# WidgetArduinoProMiniBreakout.net
KiCad netlist of a schematic drawn in EAGLE
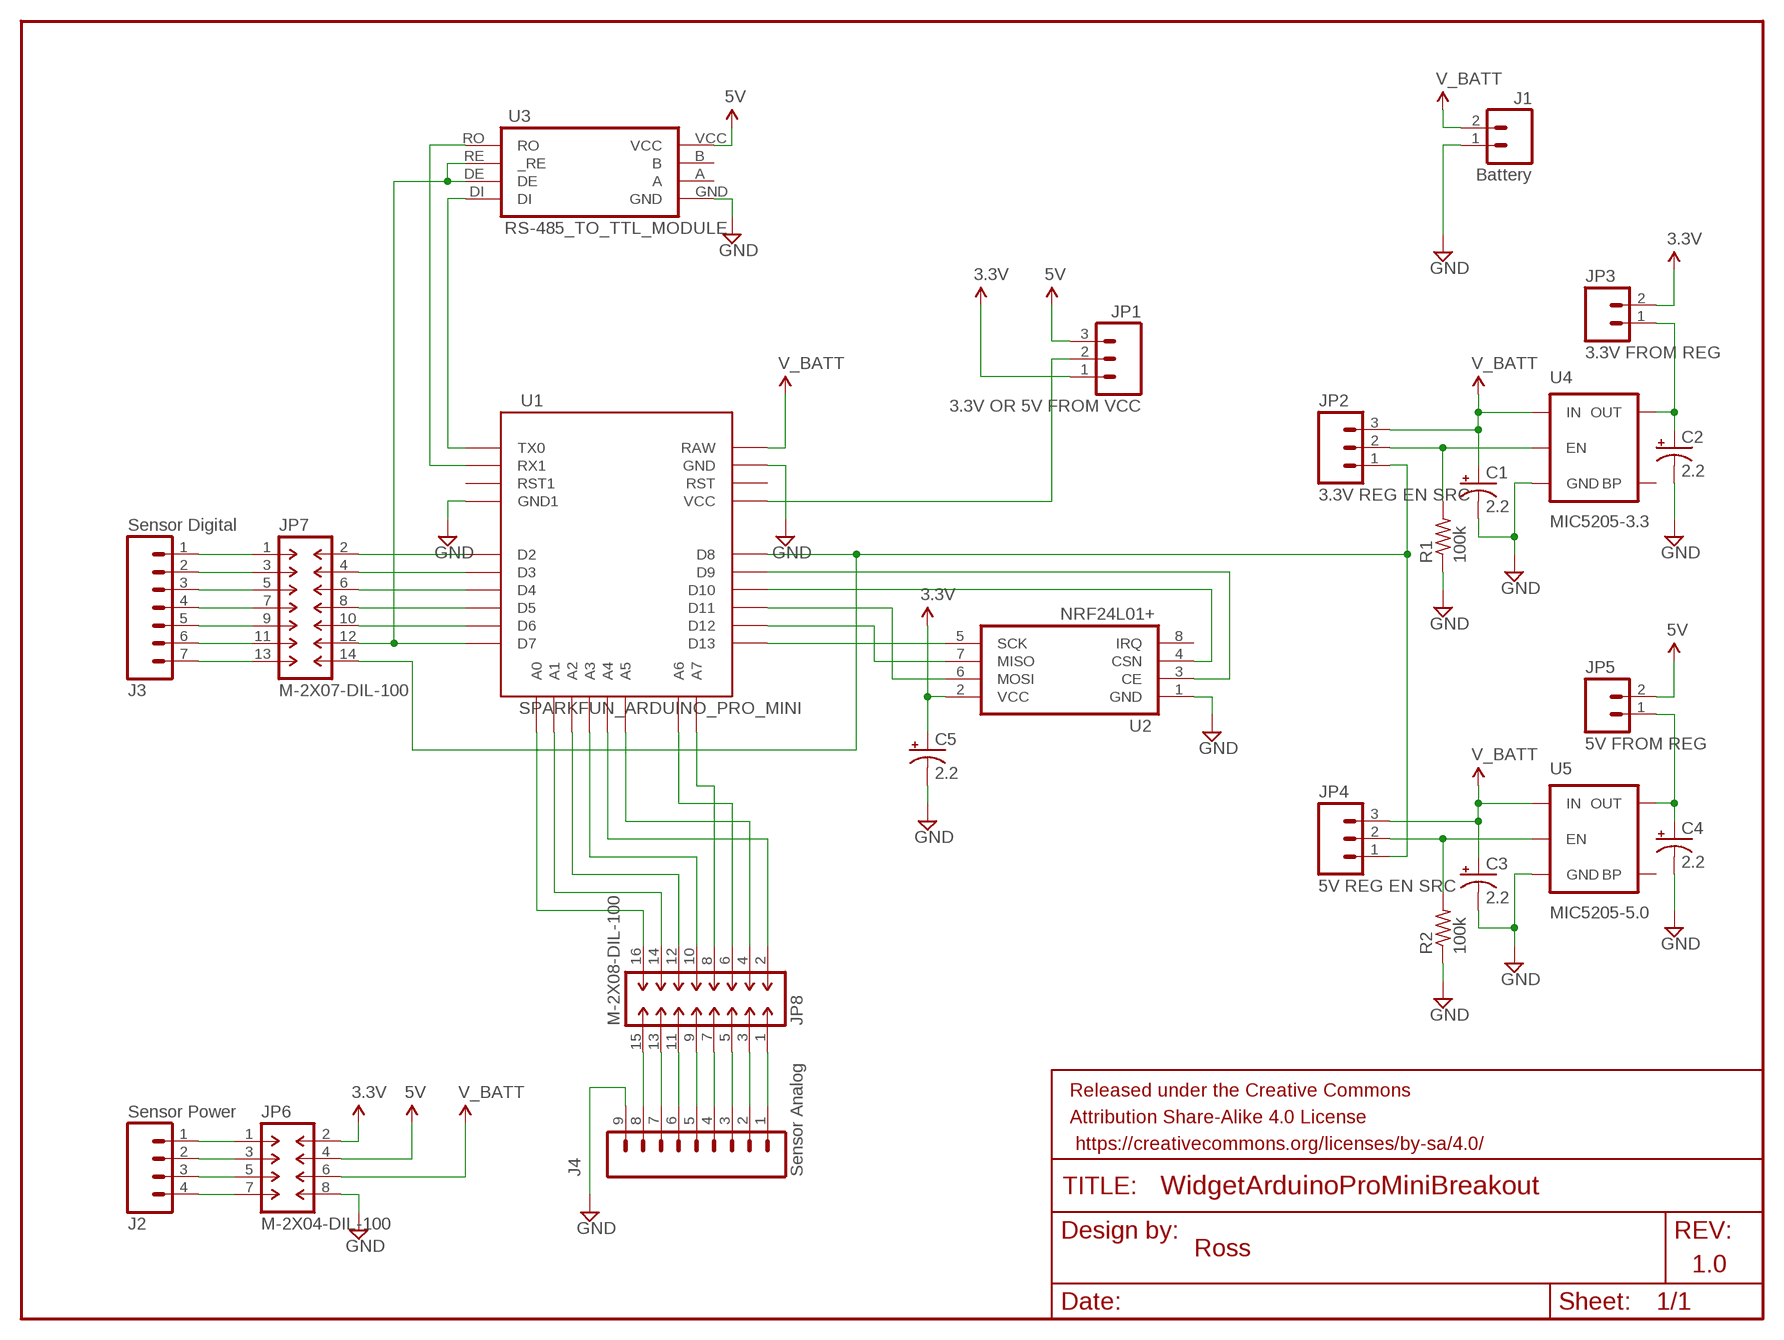
[diagram p0: schematic, sheet 1]

(export (version "E")
  (design (tool "Eeschema 10.0.6"))
  (components
    (comp (ref "C1")
      (value "2.2")
      (footprint "eagle-import:SMC_A")
      (libsource (lib "eagle-import") (part "CPOL-USSMCA"))
    )
    (comp (ref "C2")
      (value "2.2")
      (footprint "eagle-import:SMC_A")
      (libsource (lib "eagle-import") (part "CPOL-USSMCA"))
    )
    (comp (ref "C3")
      (value "2.2")
      (footprint "eagle-import:SMC_A")
      (libsource (lib "eagle-import") (part "CPOL-USSMCA"))
    )
    (comp (ref "C4")
      (value "2.2")
      (footprint "eagle-import:SMC_A")
      (libsource (lib "eagle-import") (part "CPOL-USSMCA"))
    )
    (comp (ref "C5")
      (value "2.2")
      (footprint "eagle-import:SMC_A")
      (libsource (lib "eagle-import") (part "CPOL-USSMCA"))
    )
    (comp (ref "FRAME1")
      (value "FRAME-LETTER")
      (footprint "eagle-import:CREATIVE_COMMONS")
      (libsource (lib "eagle-import") (part "FRAME-LETTER"))
    )
    (comp (ref "J1")
      (value "Battery")
      (footprint "eagle-import:JST-PH-2-TH-VERT")
      (libsource (lib "eagle-import") (part "JST-PH-2"))
    )
    (comp (ref "J2")
      (value "Sensor Power")
      (footprint "eagle-import:JST-PH-4-TH-VERT")
      (libsource (lib "eagle-import") (part "JST-PH-4"))
    )
    (comp (ref "J3")
      (value "Sensor Digital")
      (footprint "eagle-import:JST-PH-7-TH-VERT")
      (libsource (lib "eagle-import") (part "JST-PH-7"))
    )
    (comp (ref "J4")
      (value "Sensor Analog")
      (footprint "eagle-import:JST-PH-9-TH-VERT")
      (libsource (lib "eagle-import") (part "JST-PH-9"))
    )
    (comp (ref "JP1")
      (value "3.3V OR 5V FROM VCC")
      (footprint "eagle-import:1X03_LOCK_LONGPADS")
      (libsource (lib "eagle-import") (part "M03LOCK_LONGPADS"))
    )
    (comp (ref "JP2")
      (value "3.3V REG EN SRC")
      (footprint "eagle-import:1X03_LOCK_LONGPADS")
      (libsource (lib "eagle-import") (part "M03LOCK_LONGPADS"))
    )
    (comp (ref "JP3")
      (value "3.3V FROM REG")
      (footprint "eagle-import:1X02_LOCK_LONGPADS")
      (libsource (lib "eagle-import") (part "M02LOCK_LONGPADS"))
    )
    (comp (ref "JP4")
      (value "5V REG EN SRC")
      (footprint "eagle-import:1X03_LOCK_LONGPADS")
      (libsource (lib "eagle-import") (part "M03LOCK_LONGPADS"))
    )
    (comp (ref "JP5")
      (value "5V FROM REG")
      (footprint "eagle-import:1X02_LOCK_LONGPADS")
      (libsource (lib "eagle-import") (part "M02LOCK_LONGPADS"))
    )
    (comp (ref "JP6")
      (value "M-2X04-DIL-100")
      (footprint "eagle-import:DIL-100-2X04")
      (libsource (lib "eagle-import") (part "M-2X04-DIL-100"))
    )
    (comp (ref "JP7")
      (value "M-2X07-DIL-100")
      (footprint "eagle-import:DIL-100-2X07")
      (libsource (lib "eagle-import") (part "M-2X07-DIL-100"))
    )
    (comp (ref "JP8")
      (value "M-2X08-DIL-100")
      (footprint "eagle-import:DIL-100-2X08")
      (libsource (lib "eagle-import") (part "M-2X08-DIL-100"))
    )
    (comp (ref "R1")
      (value "100k")
      (footprint "eagle-import:R0603")
      (libsource (lib "eagle-import") (part "R-US_R0603"))
    )
    (comp (ref "R2")
      (value "100k")
      (footprint "eagle-import:R0603")
      (libsource (lib "eagle-import") (part "R-US_R0603"))
    )
    (comp (ref "U1")
      (value "SPARKFUN_ARDUINO_PRO_MINI")
      (footprint "eagle-import:SPARKFUN_ARDUINO_PRO_MINI")
      (libsource (lib "eagle-import") (part "SPARKFUN_ARDUINO_PRO_MINI"))
    )
    (comp (ref "U2")
      (value "NRF24L01+")
      (footprint "eagle-import:CHEAP_NRF24L01P_MODULE")
      (libsource (lib "eagle-import") (part "NRF24L01P_MODULECHEAPCHEAP"))
    )
    (comp (ref "U3")
      (value "RS-485_TO_TTL_MODULE")
      (footprint "eagle-import:RS-485_TO_TTL_MODULE")
      (libsource (lib "eagle-import") (part "RS-485_TO_TTL_MODULE"))
    )
    (comp (ref "U4")
      (value "MIC5205-3.3")
      (footprint "eagle-import:SOT23-5")
      (libsource (lib "eagle-import") (part "MIC52053.3V"))
    )
    (comp (ref "U5")
      (value "MIC5205-5.0")
      (footprint "eagle-import:SOT23-5")
      (libsource (lib "eagle-import") (part "MIC52055V"))
    )
  )
  (nets
    (net (code "1") (name "3.3V") (class "Default")
      (node (ref "C5") (pin "+") (pinfunction "+_+") (pintype "passive"))
      (node (ref "JP1") (pin "1") (pinfunction "1_1") (pintype "passive"))
      (node (ref "JP3") (pin "2") (pinfunction "2_2") (pintype "passive"))
      (node (ref "JP6") (pin "2") (pinfunction "2_2") (pintype "passive"))
      (node (ref "U2") (pin "2") (pinfunction "VCC_2") (pintype "power_in"))
    )
    (net (code "2") (name "5V") (class "Default")
      (node (ref "JP1") (pin "3") (pinfunction "3_3") (pintype "passive"))
      (node (ref "JP5") (pin "2") (pinfunction "2_2") (pintype "passive"))
      (node (ref "JP6") (pin "4") (pinfunction "4_4") (pintype "passive"))
      (node (ref "U3") (pin "VCC") (pinfunction "VCC_VCC") (pintype "power_in"))
    )
    (net (code "3") (name "GND") (class "Default")
      (node (ref "C1") (pin "-") (pinfunction "-_-") (pintype "passive"))
      (node (ref "C2") (pin "-") (pinfunction "-_-") (pintype "passive"))
      (node (ref "C3") (pin "-") (pinfunction "-_-") (pintype "passive"))
      (node (ref "C4") (pin "-") (pinfunction "-_-") (pintype "passive"))
      (node (ref "C5") (pin "-") (pinfunction "-_-") (pintype "passive"))
      (node (ref "J1") (pin "1") (pinfunction "1_1") (pintype "passive"))
      (node (ref "J4") (pin "9") (pinfunction "9_9") (pintype "passive"))
      (node (ref "JP6") (pin "8") (pinfunction "8_8") (pintype "passive"))
      (node (ref "R1") (pin "1") (pinfunction "1_1") (pintype "passive"))
      (node (ref "R2") (pin "1") (pinfunction "1_1") (pintype "passive"))
      (node (ref "U1") (pin "GND") (pinfunction "GND_GND") (pintype "bidirectional"))
      (node (ref "U1") (pin "GND1") (pinfunction "GND1_GND1") (pintype "bidirectional"))
      (node (ref "U2") (pin "1") (pinfunction "GND_1") (pintype "power_in"))
      (node (ref "U3") (pin "GND") (pinfunction "GND_GND") (pintype "power_in"))
      (node (ref "U4") (pin "2") (pinfunction "GND_2") (pintype "input"))
      (node (ref "U5") (pin "2") (pinfunction "GND_2") (pintype "input"))
    )
    (net (code "4") (name "Net-(J2-Pad1)") (class "Default")
      (node (ref "J2") (pin "1") (pinfunction "1_1") (pintype "passive"))
      (node (ref "JP6") (pin "1") (pinfunction "1_1") (pintype "passive"))
    )
    (net (code "5") (name "Net-(J2-Pad2)") (class "Default")
      (node (ref "J2") (pin "2") (pinfunction "2_2") (pintype "passive"))
      (node (ref "JP6") (pin "3") (pinfunction "3_3") (pintype "passive"))
    )
    (net (code "6") (name "Net-(J2-Pad3)") (class "Default")
      (node (ref "J2") (pin "3") (pinfunction "3_3") (pintype "passive"))
      (node (ref "JP6") (pin "5") (pinfunction "5_5") (pintype "passive"))
    )
    (net (code "7") (name "Net-(J2-Pad4)") (class "Default")
      (node (ref "J2") (pin "4") (pinfunction "4_4") (pintype "passive"))
      (node (ref "JP6") (pin "7") (pinfunction "7_7") (pintype "passive"))
    )
    (net (code "8") (name "Net-(J3-Pad1)") (class "Default")
      (node (ref "J3") (pin "1") (pinfunction "1_1") (pintype "passive"))
      (node (ref "JP7") (pin "1") (pinfunction "1_1") (pintype "passive"))
    )
    (net (code "9") (name "Net-(J3-Pad2)") (class "Default")
      (node (ref "J3") (pin "2") (pinfunction "2_2") (pintype "passive"))
      (node (ref "JP7") (pin "3") (pinfunction "3_3") (pintype "passive"))
    )
    (net (code "10") (name "Net-(J3-Pad3)") (class "Default")
      (node (ref "J3") (pin "3") (pinfunction "3_3") (pintype "passive"))
      (node (ref "JP7") (pin "5") (pinfunction "5_5") (pintype "passive"))
    )
    (net (code "11") (name "Net-(J3-Pad4)") (class "Default")
      (node (ref "J3") (pin "4") (pinfunction "4_4") (pintype "passive"))
      (node (ref "JP7") (pin "7") (pinfunction "7_7") (pintype "passive"))
    )
    (net (code "12") (name "Net-(J3-Pad5)") (class "Default")
      (node (ref "J3") (pin "5") (pinfunction "5_5") (pintype "passive"))
      (node (ref "JP7") (pin "9") (pinfunction "9_9") (pintype "passive"))
    )
    (net (code "13") (name "Net-(J3-Pad6)") (class "Default")
      (node (ref "J3") (pin "6") (pinfunction "6_6") (pintype "passive"))
      (node (ref "JP7") (pin "11") (pinfunction "11_11") (pintype "passive"))
    )
    (net (code "14") (name "Net-(J3-Pad7)") (class "Default")
      (node (ref "J3") (pin "7") (pinfunction "7_7") (pintype "passive"))
      (node (ref "JP7") (pin "13") (pinfunction "13_13") (pintype "passive"))
    )
    (net (code "15") (name "Net-(J4-Pad1)") (class "Default")
      (node (ref "J4") (pin "1") (pinfunction "1_1") (pintype "passive"))
      (node (ref "JP8") (pin "1") (pinfunction "1_1") (pintype "passive"))
    )
    (net (code "16") (name "Net-(J4-Pad2)") (class "Default")
      (node (ref "J4") (pin "2") (pinfunction "2_2") (pintype "passive"))
      (node (ref "JP8") (pin "3") (pinfunction "3_3") (pintype "passive"))
    )
    (net (code "17") (name "Net-(J4-Pad3)") (class "Default")
      (node (ref "J4") (pin "3") (pinfunction "3_3") (pintype "passive"))
      (node (ref "JP8") (pin "5") (pinfunction "5_5") (pintype "passive"))
    )
    (net (code "18") (name "Net-(J4-Pad4)") (class "Default")
      (node (ref "J4") (pin "4") (pinfunction "4_4") (pintype "passive"))
      (node (ref "JP8") (pin "7") (pinfunction "7_7") (pintype "passive"))
    )
    (net (code "19") (name "Net-(J4-Pad5)") (class "Default")
      (node (ref "J4") (pin "5") (pinfunction "5_5") (pintype "passive"))
      (node (ref "JP8") (pin "9") (pinfunction "9_9") (pintype "passive"))
    )
    (net (code "20") (name "Net-(J4-Pad6)") (class "Default")
      (node (ref "J4") (pin "6") (pinfunction "6_6") (pintype "passive"))
      (node (ref "JP8") (pin "11") (pinfunction "11_11") (pintype "passive"))
    )
    (net (code "21") (name "Net-(J4-Pad7)") (class "Default")
      (node (ref "J4") (pin "7") (pinfunction "7_7") (pintype "passive"))
      (node (ref "JP8") (pin "13") (pinfunction "13_13") (pintype "passive"))
    )
    (net (code "22") (name "Net-(J4-Pad8)") (class "Default")
      (node (ref "J4") (pin "8") (pinfunction "8_8") (pintype "passive"))
      (node (ref "JP8") (pin "15") (pinfunction "15_15") (pintype "passive"))
    )
    (net (code "23") (name "Net-(JP1-Pad2)") (class "Default")
      (node (ref "JP1") (pin "2") (pinfunction "2_2") (pintype "passive"))
      (node (ref "U1") (pin "VCC") (pinfunction "VCC_VCC") (pintype "bidirectional"))
    )
    (net (code "24") (name "Net-(JP2-Pad1)") (class "Default")
      (node (ref "JP2") (pin "1") (pinfunction "1_1") (pintype "passive"))
      (node (ref "JP4") (pin "1") (pinfunction "1_1") (pintype "passive"))
      (node (ref "JP7") (pin "14") (pinfunction "14_14") (pintype "passive"))
      (node (ref "U1") (pin "D8") (pinfunction "D8_D8") (pintype "bidirectional"))
    )
    (net (code "25") (name "Net-(JP7-Pad2)") (class "Default")
      (node (ref "JP7") (pin "2") (pinfunction "2_2") (pintype "passive"))
      (node (ref "U1") (pin "D2") (pinfunction "D2_D2") (pintype "bidirectional"))
    )
    (net (code "26") (name "Net-(JP7-Pad4)") (class "Default")
      (node (ref "JP7") (pin "4") (pinfunction "4_4") (pintype "passive"))
      (node (ref "U1") (pin "D3") (pinfunction "D3_D3") (pintype "bidirectional"))
    )
    (net (code "27") (name "Net-(JP7-Pad6)") (class "Default")
      (node (ref "JP7") (pin "6") (pinfunction "6_6") (pintype "passive"))
      (node (ref "U1") (pin "D4") (pinfunction "D4_D4") (pintype "bidirectional"))
    )
    (net (code "28") (name "Net-(JP7-Pad8)") (class "Default")
      (node (ref "JP7") (pin "8") (pinfunction "8_8") (pintype "passive"))
      (node (ref "U1") (pin "D5") (pinfunction "D5_D5") (pintype "bidirectional"))
    )
    (net (code "29") (name "Net-(JP7-Pad10)") (class "Default")
      (node (ref "JP7") (pin "10") (pinfunction "10_10") (pintype "passive"))
      (node (ref "U1") (pin "D6") (pinfunction "D6_D6") (pintype "bidirectional"))
    )
    (net (code "30") (name "Net-(JP8-Pad2)") (class "Default")
      (node (ref "JP8") (pin "2") (pinfunction "2_2") (pintype "passive"))
      (node (ref "U1") (pin "A4") (pinfunction "A4_A4") (pintype "bidirectional"))
    )
    (net (code "31") (name "Net-(JP8-Pad4)") (class "Default")
      (node (ref "JP8") (pin "4") (pinfunction "4_4") (pintype "passive"))
      (node (ref "U1") (pin "A5") (pinfunction "A5_A5") (pintype "bidirectional"))
    )
    (net (code "32") (name "Net-(JP8-Pad6)") (class "Default")
      (node (ref "JP8") (pin "6") (pinfunction "6_6") (pintype "passive"))
      (node (ref "U1") (pin "A6") (pinfunction "A6_A6") (pintype "bidirectional"))
    )
    (net (code "33") (name "Net-(JP8-Pad8)") (class "Default")
      (node (ref "JP8") (pin "8") (pinfunction "8_8") (pintype "passive"))
      (node (ref "U1") (pin "A7") (pinfunction "A7_A7") (pintype "bidirectional"))
    )
    (net (code "34") (name "Net-(JP8-Pad10)") (class "Default")
      (node (ref "JP8") (pin "10") (pinfunction "10_10") (pintype "passive"))
      (node (ref "U1") (pin "A3") (pinfunction "A3_A3") (pintype "bidirectional"))
    )
    (net (code "35") (name "Net-(JP8-Pad12)") (class "Default")
      (node (ref "JP8") (pin "12") (pinfunction "12_12") (pintype "passive"))
      (node (ref "U1") (pin "A2") (pinfunction "A2_A2") (pintype "bidirectional"))
    )
    (net (code "36") (name "Net-(JP8-Pad14)") (class "Default")
      (node (ref "JP8") (pin "14") (pinfunction "14_14") (pintype "passive"))
      (node (ref "U1") (pin "A1") (pinfunction "A1_A1") (pintype "bidirectional"))
    )
    (net (code "37") (name "Net-(JP8-Pad16)") (class "Default")
      (node (ref "JP8") (pin "16") (pinfunction "16_16") (pintype "passive"))
      (node (ref "U1") (pin "A0") (pinfunction "A0_A0") (pintype "bidirectional"))
    )
    (net (code "38") (name "Net-(U1-PadRX1)") (class "Default")
      (node (ref "U1") (pin "RX1") (pinfunction "RX1_RX1") (pintype "bidirectional"))
      (node (ref "U3") (pin "RO") (pinfunction "RO_RO") (pintype "output"))
    )
    (net (code "39") (name "Net-(U1-PadTX0)") (class "Default")
      (node (ref "U1") (pin "TX0") (pinfunction "TX0_TX0") (pintype "bidirectional"))
      (node (ref "U3") (pin "DI") (pinfunction "DI_DI") (pintype "input"))
    )
    (net (code "40") (name "Net-(U2-CE)") (class "Default")
      (node (ref "U1") (pin "D9") (pinfunction "D9_D9") (pintype "bidirectional"))
      (node (ref "U2") (pin "3") (pinfunction "CE_3") (pintype "input"))
    )
    (net (code "41") (name "Net-(U2-CSN)") (class "Default")
      (node (ref "U1") (pin "D10") (pinfunction "D10_D10") (pintype "bidirectional"))
      (node (ref "U2") (pin "4") (pinfunction "CSN_4") (pintype "input"))
    )
    (net (code "42") (name "Net-(U2-MISO)") (class "Default")
      (node (ref "U1") (pin "D12") (pinfunction "D12_D12") (pintype "bidirectional"))
      (node (ref "U2") (pin "7") (pinfunction "MISO_7") (pintype "output"))
    )
    (net (code "43") (name "Net-(U2-MOSI)") (class "Default")
      (node (ref "U1") (pin "D11") (pinfunction "D11_D11") (pintype "bidirectional"))
      (node (ref "U2") (pin "6") (pinfunction "MOSI_6") (pintype "input"))
    )
    (net (code "44") (name "Net-(U2-SCK)") (class "Default")
      (node (ref "U1") (pin "D13") (pinfunction "D13_D13") (pintype "bidirectional"))
      (node (ref "U2") (pin "5") (pinfunction "SCK_5") (pintype "input"))
    )
    (net (code "45") (name "Net-(U3-_RE)") (class "Default")
      (node (ref "JP7") (pin "12") (pinfunction "12_12") (pintype "passive"))
      (node (ref "U1") (pin "D7") (pinfunction "D7_D7") (pintype "bidirectional"))
      (node (ref "U3") (pin "DE") (pinfunction "DE_DE") (pintype "input"))
      (node (ref "U3") (pin "RE") (pinfunction "_RE_RE") (pintype "input"))
    )
    (net (code "46") (name "Net-(U4-EN)") (class "Default")
      (node (ref "JP2") (pin "2") (pinfunction "2_2") (pintype "passive"))
      (node (ref "R1") (pin "2") (pinfunction "2_2") (pintype "passive"))
      (node (ref "U4") (pin "3") (pinfunction "EN_3") (pintype "input"))
    )
    (net (code "47") (name "Net-(U4-OUT)") (class "Default")
      (node (ref "C2") (pin "+") (pinfunction "+_+") (pintype "passive"))
      (node (ref "JP3") (pin "1") (pinfunction "1_1") (pintype "passive"))
      (node (ref "U4") (pin "5") (pinfunction "OUT_5") (pintype "passive"))
    )
    (net (code "48") (name "Net-(U5-EN)") (class "Default")
      (node (ref "JP4") (pin "2") (pinfunction "2_2") (pintype "passive"))
      (node (ref "R2") (pin "2") (pinfunction "2_2") (pintype "passive"))
      (node (ref "U5") (pin "3") (pinfunction "EN_3") (pintype "input"))
    )
    (net (code "49") (name "Net-(U5-OUT)") (class "Default")
      (node (ref "C4") (pin "+") (pinfunction "+_+") (pintype "passive"))
      (node (ref "JP5") (pin "1") (pinfunction "1_1") (pintype "passive"))
      (node (ref "U5") (pin "5") (pinfunction "OUT_5") (pintype "passive"))
    )
    (net (code "50") (name "V_BATT") (class "Default")
      (node (ref "C1") (pin "+") (pinfunction "+_+") (pintype "passive"))
      (node (ref "C3") (pin "+") (pinfunction "+_+") (pintype "passive"))
      (node (ref "J1") (pin "2") (pinfunction "2_2") (pintype "passive"))
      (node (ref "JP2") (pin "3") (pinfunction "3_3") (pintype "passive"))
      (node (ref "JP4") (pin "3") (pinfunction "3_3") (pintype "passive"))
      (node (ref "JP6") (pin "6") (pinfunction "6_6") (pintype "passive"))
      (node (ref "U1") (pin "RAW") (pinfunction "RAW_RAW") (pintype "bidirectional"))
      (node (ref "U4") (pin "1") (pinfunction "IN_1") (pintype "input"))
      (node (ref "U5") (pin "1") (pinfunction "IN_1") (pintype "input"))
    )
    (net (code "51") (name "unconnected-(U1-PadRST)") (class "Default")
      (node (ref "U1") (pin "RST") (pinfunction "RST_RST") (pintype "bidirectional"))
    )
    (net (code "52") (name "unconnected-(U1-PadRST1)") (class "Default")
      (node (ref "U1") (pin "RST1") (pinfunction "RST1_RST1") (pintype "bidirectional"))
    )
    (net (code "53") (name "unconnected-(U2-IRQ-Pad8)") (class "Default")
      (node (ref "U2") (pin "8") (pinfunction "IRQ_8") (pintype "bidirectional"))
    )
    (net (code "54") (name "unconnected-(U3-PadA)") (class "Default")
      (node (ref "U3") (pin "A") (pinfunction "A_A") (pintype "bidirectional"))
    )
    (net (code "55") (name "unconnected-(U3-PadB)") (class "Default")
      (node (ref "U3") (pin "B") (pinfunction "B_B") (pintype "bidirectional"))
    )
    (net (code "56") (name "unconnected-(U4-BP-Pad4)") (class "Default")
      (node (ref "U4") (pin "4") (pinfunction "BP_4") (pintype "input"))
    )
    (net (code "57") (name "unconnected-(U5-BP-Pad4)") (class "Default")
      (node (ref "U5") (pin "4") (pinfunction "BP_4") (pintype "input"))
    )
  )
)
